# phone-finder.net
KiCad netlist of a schematic drawn in EAGLE
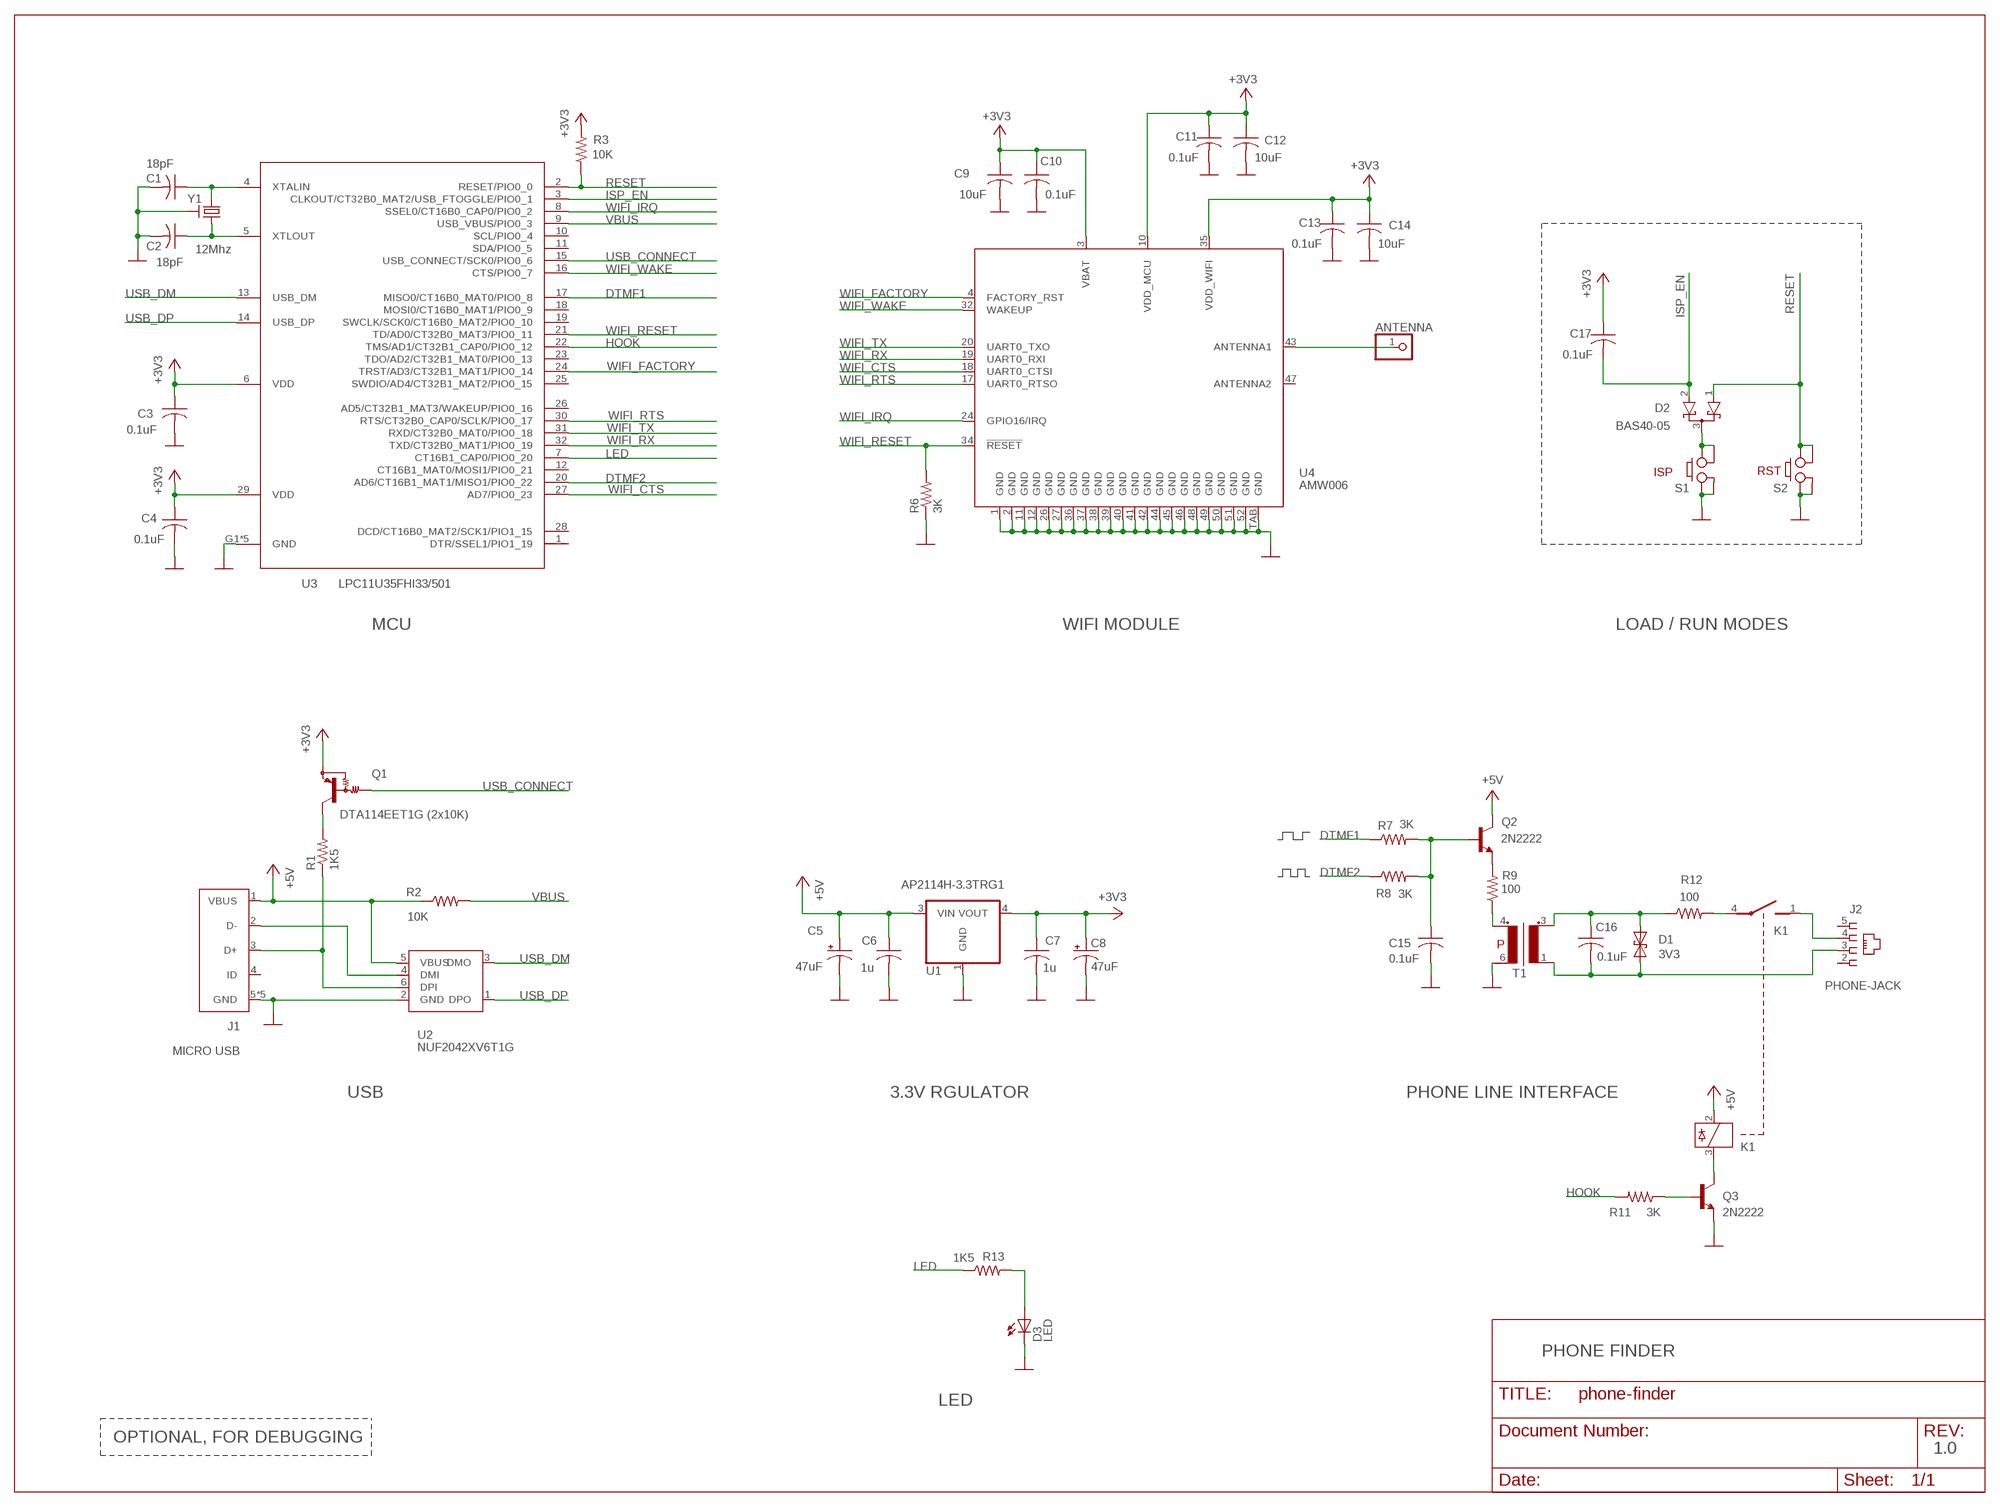
[diagram p0: schematic, sheet 1]

(export (version "E")
  (design (tool "Eeschema 10.0.6"))
  (components
    (comp (ref "ANTENNA")
      (value "PINHD-1X1")
      (footprint "eagle-import:PINHD-1X1")
      (libsource (lib "eagle-import") (part "PINHD-1X1"))
    )
    (comp (ref "C1")
      (value "18pF")
      (footprint "eagle-import:C0402K")
      (libsource (lib "eagle-import") (part "CC0402K"))
    )
    (comp (ref "C2")
      (value "18pF")
      (footprint "eagle-import:C0402K")
      (libsource (lib "eagle-import") (part "CC0402K"))
    )
    (comp (ref "C3")
      (value "0.1uF")
      (footprint "eagle-import:C0402K")
      (libsource (lib "eagle-import") (part "CC0402K"))
    )
    (comp (ref "C4")
      (value "0.1uF")
      (footprint "eagle-import:C0402K")
      (libsource (lib "eagle-import") (part "CC0402K"))
    )
    (comp (ref "C5")
      (value "47uF")
      (footprint "eagle-import:UD-6,3X5,8_NICHICON")
      (libsource (lib "eagle-import") (part "C-POLUD-6,3X5,8"))
    )
    (comp (ref "C6")
      (value "1u")
      (footprint "eagle-import:C0603K")
      (libsource (lib "eagle-import") (part "CC0603K"))
    )
    (comp (ref "C7")
      (value "1u")
      (footprint "eagle-import:C0603K")
      (libsource (lib "eagle-import") (part "CC0603K"))
    )
    (comp (ref "C8")
      (value "47uF")
      (footprint "eagle-import:UD-6,3X5,8_NICHICON")
      (libsource (lib "eagle-import") (part "C-POLUD-6,3X5,8"))
    )
    (comp (ref "C9")
      (value "10uF")
      (footprint "eagle-import:C0805K")
      (libsource (lib "eagle-import") (part "CC0805K"))
    )
    (comp (ref "C10")
      (value "0.1uF")
      (footprint "eagle-import:C0402K")
      (libsource (lib "eagle-import") (part "CC0402K"))
    )
    (comp (ref "C11")
      (value "0.1uF")
      (footprint "eagle-import:C0402K")
      (libsource (lib "eagle-import") (part "CC0402K"))
    )
    (comp (ref "C12")
      (value "10uF")
      (footprint "eagle-import:C0805K")
      (libsource (lib "eagle-import") (part "CC0805K"))
    )
    (comp (ref "C13")
      (value "0.1uF")
      (footprint "eagle-import:C0402K")
      (libsource (lib "eagle-import") (part "CC0402K"))
    )
    (comp (ref "C14")
      (value "10uF")
      (footprint "eagle-import:C0805K")
      (libsource (lib "eagle-import") (part "CC0805K"))
    )
    (comp (ref "C15")
      (value "0.1uF")
      (footprint "eagle-import:C0402K")
      (libsource (lib "eagle-import") (part "CC0402K"))
    )
    (comp (ref "C16")
      (value "0.1uF")
      (footprint "eagle-import:C0402K")
      (libsource (lib "eagle-import") (part "CC0402K"))
    )
    (comp (ref "C17")
      (value "0.1uF")
      (footprint "eagle-import:C0402K")
      (libsource (lib "eagle-import") (part "CC0402K"))
    )
    (comp (ref "D1")
      (value "3V3")
      (footprint "eagle-import:DZ-0402")
      (libsource (lib "eagle-import") (part "DUAL-ZENER"))
    )
    (comp (ref "D2")
      (value "BAS40-05")
      (footprint "eagle-import:SOT23")
      (libsource (lib "eagle-import") (part "BAS40-05"))
    )
    (comp (ref "D3")
      (value "LED")
      (footprint "eagle-import:LED")
      (libsource (lib "eagle-import") (part "LED"))
    )
    (comp (ref "J1")
      (value "MICRO USB")
      (footprint "eagle-import:USB-MICRO")
      (libsource (lib "eagle-import") (part "USB-CONN"))
    )
    (comp (ref "J2")
      (value "PHONE-JACK")
      (footprint "eagle-import:PHONE-JACK")
      (libsource (lib "eagle-import") (part "PHONE-JACK"))
    )
    (comp (ref "K1")
      (value "RELAY")
      (footprint "eagle-import:RELAY")
      (libsource (lib "eagle-import") (part "RELAY"))
    )
    (comp (ref "Q1")
      (value "DTA114EET1G (2x10K)")
      (footprint "eagle-import:SC75-BEC")
      (libsource (lib "eagle-import") (part "PNP-BIASED"))
    )
    (comp (ref "Q2")
      (value "2N2222")
      (footprint "eagle-import:SOT23")
      (libsource (lib "eagle-import") (part "NPN"))
    )
    (comp (ref "Q3")
      (value "2N2222")
      (footprint "eagle-import:SOT23")
      (libsource (lib "eagle-import") (part "NPN"))
    )
    (comp (ref "R1")
      (value "1K5")
      (footprint "eagle-import:R0402")
      (libsource (lib "eagle-import") (part "RR0402"))
    )
    (comp (ref "R2")
      (value "10K")
      (footprint "eagle-import:R0402")
      (libsource (lib "eagle-import") (part "RR0402"))
    )
    (comp (ref "R3")
      (value "10K")
      (footprint "eagle-import:R0402")
      (libsource (lib "eagle-import") (part "RR0402"))
    )
    (comp (ref "R6")
      (value "3K")
      (footprint "eagle-import:R0402")
      (libsource (lib "eagle-import") (part "RR0402"))
    )
    (comp (ref "R7")
      (value "3K")
      (footprint "eagle-import:R0402")
      (libsource (lib "eagle-import") (part "RR0402"))
    )
    (comp (ref "R8")
      (value "3K")
      (footprint "eagle-import:R0402")
      (libsource (lib "eagle-import") (part "RR0402"))
    )
    (comp (ref "R9")
      (value "100")
      (footprint "eagle-import:R0805")
      (libsource (lib "eagle-import") (part "RR0805"))
    )
    (comp (ref "R11")
      (value "3K")
      (footprint "eagle-import:R0402")
      (libsource (lib "eagle-import") (part "RR0402"))
    )
    (comp (ref "R12")
      (value "100")
      (footprint "eagle-import:R0805")
      (libsource (lib "eagle-import") (part "RR0805"))
    )
    (comp (ref "R13")
      (value "1K5")
      (footprint "eagle-import:R0402")
      (libsource (lib "eagle-import") (part "RR0402"))
    )
    (comp (ref "S1")
      (value "PUSH-BUTTON")
      (footprint "eagle-import:PUSH_BUTTON")
      (libsource (lib "eagle-import") (part "PUSH-BUTTON"))
    )
    (comp (ref "S2")
      (value "PUSH-BUTTON")
      (footprint "eagle-import:PUSH_BUTTON")
      (libsource (lib "eagle-import") (part "PUSH-BUTTON"))
    )
    (comp (ref "T1")
      (value "TRANSFORMER")
      (footprint "eagle-import:TRANSFORMER")
      (libsource (lib "eagle-import") (part "TRANSFORMER"))
    )
    (comp (ref "U1")
      (value "AP2114H-3.3TRG1")
      (footprint "eagle-import:SOT223")
      (libsource (lib "eagle-import") (part "LDOSOT223"))
    )
    (comp (ref "U2")
      (value "NUF2042XV6T1G")
      (footprint "eagle-import:SOT-563")
      (libsource (lib "eagle-import") (part "USB-ESD"))
    )
    (comp (ref "U3")
      (value "LPC11U35FHI33/501")
      (footprint "eagle-import:HVQFN33-5MM")
      (libsource (lib "eagle-import") (part "LPC11U35FHN33/501"))
    )
    (comp (ref "U4")
      (value "AMW006")
      (footprint "eagle-import:WIFI_MODULE")
      (libsource (lib "eagle-import") (part "WIFI-MODULESMT"))
    )
    (comp (ref "Y1")
      (value "12Mhz")
      (footprint "eagle-import:CRYSTAL")
      (libsource (lib "eagle-import") (part "CRYSTALCTS406"))
    )
  )
  (nets
    (net (code "1") (name "+3V3") (class "Default")
      (node (ref "C10") (pin "1") (pinfunction "1_1") (pintype "passive"))
      (node (ref "C11") (pin "1") (pinfunction "1_1") (pintype "passive"))
      (node (ref "C12") (pin "1") (pinfunction "1_1") (pintype "passive"))
      (node (ref "C13") (pin "1") (pinfunction "1_1") (pintype "passive"))
      (node (ref "C14") (pin "1") (pinfunction "1_1") (pintype "passive"))
      (node (ref "C17") (pin "1") (pinfunction "1_1") (pintype "passive"))
      (node (ref "C3") (pin "1") (pinfunction "1_1") (pintype "passive"))
      (node (ref "C4") (pin "1") (pinfunction "1_1") (pintype "passive"))
      (node (ref "C7") (pin "1") (pinfunction "1_1") (pintype "passive"))
      (node (ref "C8") (pin "+") (pinfunction "+_+") (pintype "passive"))
      (node (ref "C9") (pin "1") (pinfunction "1_1") (pintype "passive"))
      (node (ref "Q1") (pin "E") (pinfunction "E_E") (pintype "passive"))
      (node (ref "R3") (pin "2") (pinfunction "2_2") (pintype "passive"))
      (node (ref "U1") (pin "4") (pinfunction "VOUT_4") (pintype "power_in"))
      (node (ref "U3") (pin "29") (pinfunction "VDD_29") (pintype "bidirectional"))
      (node (ref "U3") (pin "6") (pinfunction "VDD_6") (pintype "bidirectional"))
      (node (ref "U4") (pin "10") (pinfunction "VDD_MCU_10") (pintype "power_in"))
      (node (ref "U4") (pin "3") (pinfunction "VBAT_3") (pintype "power_in"))
      (node (ref "U4") (pin "35") (pinfunction "VDD_WIFI_35") (pintype "power_in"))
    )
    (net (code "2") (name "+5V") (class "Default")
      (node (ref "C5") (pin "+") (pinfunction "+_+") (pintype "passive"))
      (node (ref "C6") (pin "1") (pinfunction "1_1") (pintype "passive"))
      (node (ref "J1") (pin "1") (pinfunction "VBUS_1") (pintype "bidirectional"))
      (node (ref "K1") (pin "2") (pinfunction "COIL-POS_2") (pintype "passive"))
      (node (ref "Q2") (pin "3") (pinfunction "C_3") (pintype "passive"))
      (node (ref "R2") (pin "1") (pinfunction "1_1") (pintype "passive"))
      (node (ref "U1") (pin "3") (pinfunction "VIN_3") (pintype "power_in"))
      (node (ref "U2") (pin "5") (pinfunction "VBUS_5") (pintype "power_in"))
    )
    (net (code "3") (name "/DTMF1") (class "Default")
      (node (ref "R7") (pin "1") (pinfunction "1_1") (pintype "passive"))
      (node (ref "U3") (pin "17") (pinfunction "MISO0/CT16B0_MAT0/PIO0_8_17") (pintype "bidirectional"))
    )
    (net (code "4") (name "/DTMF2") (class "Default")
      (node (ref "R8") (pin "1") (pinfunction "1_1") (pintype "passive"))
      (node (ref "U3") (pin "20") (pinfunction "AD6/CT16B1_MAT1/MISO1/PIO0_22_20") (pintype "bidirectional"))
    )
    (net (code "5") (name "/HOOK") (class "Default")
      (node (ref "R11") (pin "2") (pinfunction "2_2") (pintype "passive"))
      (node (ref "U3") (pin "22") (pinfunction "TMS/AD1/CT32B1_CAP0/PIO0_12_22") (pintype "bidirectional"))
    )
    (net (code "6") (name "/ISP_EN") (class "Default")
      (node (ref "C17") (pin "2") (pinfunction "2_2") (pintype "passive"))
      (node (ref "D2") (pin "2") (pinfunction "A2_2") (pintype "passive"))
      (node (ref "U3") (pin "3") (pinfunction "CLKOUT/CT32B0_MAT2/USB_FTOGGLE/PIO0_1_3") (pintype "bidirectional"))
    )
    (net (code "7") (name "/LED") (class "Default")
      (node (ref "R13") (pin "1") (pinfunction "1_1") (pintype "passive"))
      (node (ref "U3") (pin "7") (pinfunction "CT16B1_CAP0/PIO0_20_7") (pintype "bidirectional"))
    )
    (net (code "8") (name "/RESET") (class "Default")
      (node (ref "D2") (pin "1") (pinfunction "A1_1") (pintype "passive"))
      (node (ref "R3") (pin "1") (pinfunction "1_1") (pintype "passive"))
      (node (ref "S2") (pin "B1") (pinfunction "B1_B1") (pintype "passive"))
      (node (ref "S2") (pin "B1P") (pinfunction "B1_B1P") (pintype "passive"))
      (node (ref "S2") (pin "B2") (pinfunction "B2_B2") (pintype "passive"))
      (node (ref "S2") (pin "B2P") (pinfunction "B2_B2P") (pintype "passive"))
      (node (ref "U3") (pin "2") (pinfunction "RESET/PIO0_0_2") (pintype "bidirectional"))
    )
    (net (code "9") (name "/USB_CONNECT") (class "Default")
      (node (ref "Q1") (pin "B") (pinfunction "B_B") (pintype "passive"))
      (node (ref "U3") (pin "15") (pinfunction "USB_CONNECT/SCK0/PIO0_6_15") (pintype "bidirectional"))
    )
    (net (code "10") (name "/USB_DM") (class "Default")
      (node (ref "U2") (pin "3") (pinfunction "DMO_3") (pintype "passive"))
      (node (ref "U3") (pin "13") (pinfunction "USB_DM_13") (pintype "bidirectional"))
    )
    (net (code "11") (name "/USB_DP") (class "Default")
      (node (ref "U2") (pin "1") (pinfunction "DPO_1") (pintype "passive"))
      (node (ref "U3") (pin "14") (pinfunction "USB_DP_14") (pintype "bidirectional"))
    )
    (net (code "12") (name "/VBUS") (class "Default")
      (node (ref "R2") (pin "2") (pinfunction "2_2") (pintype "passive"))
      (node (ref "U3") (pin "9") (pinfunction "USB_VBUS/PIO0_3_9") (pintype "bidirectional"))
    )
    (net (code "13") (name "/WIFI_CTS") (class "Default")
      (node (ref "U3") (pin "27") (pinfunction "AD7/PIO0_23_27") (pintype "bidirectional"))
      (node (ref "U4") (pin "18") (pinfunction "UART0_CTSI_18") (pintype "input"))
    )
    (net (code "14") (name "/WIFI_FACTORY") (class "Default")
      (node (ref "U3") (pin "24") (pinfunction "TRST/AD3/CT32B1_MAT1/PIO0_14_24") (pintype "bidirectional"))
      (node (ref "U4") (pin "4") (pinfunction "FACTORY_RST_4") (pintype "input"))
    )
    (net (code "15") (name "/WIFI_IRQ") (class "Default")
      (node (ref "U3") (pin "8") (pinfunction "SSEL0/CT16B0_CAP0/PIO0_2_8") (pintype "bidirectional"))
      (node (ref "U4") (pin "24") (pinfunction "GPIO16/IRQ_24") (pintype "output"))
    )
    (net (code "16") (name "/WIFI_RESET") (class "Default")
      (node (ref "R6") (pin "2") (pinfunction "2_2") (pintype "passive"))
      (node (ref "U3") (pin "21") (pinfunction "TD/AD0/CT32B0_MAT3/PIO0_11_21") (pintype "bidirectional"))
      (node (ref "U4") (pin "34") (pinfunction "~{RESET}_34") (pintype "input"))
    )
    (net (code "17") (name "/WIFI_RTS") (class "Default")
      (node (ref "U3") (pin "30") (pinfunction "RTS/CT32B0_CAP0/SCLK/PIO0_17_30") (pintype "bidirectional"))
      (node (ref "U4") (pin "17") (pinfunction "UART0_RTSO_17") (pintype "output"))
    )
    (net (code "18") (name "/WIFI_RX") (class "Default")
      (node (ref "U3") (pin "32") (pinfunction "TXD/CT32B0_MAT1/PIO0_19_32") (pintype "bidirectional"))
      (node (ref "U4") (pin "19") (pinfunction "UART0_RXI_19") (pintype "input"))
    )
    (net (code "19") (name "/WIFI_TX") (class "Default")
      (node (ref "U3") (pin "31") (pinfunction "RXD/CT32B0_MAT0/PIO0_18_31") (pintype "bidirectional"))
      (node (ref "U4") (pin "20") (pinfunction "UART0_TXO_20") (pintype "output"))
    )
    (net (code "20") (name "/WIFI_WAKE") (class "Default")
      (node (ref "U3") (pin "16") (pinfunction "CTS/PIO0_7_16") (pintype "bidirectional"))
      (node (ref "U4") (pin "32") (pinfunction "WAKEUP_32") (pintype "input"))
    )
    (net (code "21") (name "GND") (class "Default")
      (node (ref "C1") (pin "2") (pinfunction "2_2") (pintype "passive"))
      (node (ref "C10") (pin "2") (pinfunction "2_2") (pintype "passive"))
      (node (ref "C11") (pin "2") (pinfunction "2_2") (pintype "passive"))
      (node (ref "C12") (pin "2") (pinfunction "2_2") (pintype "passive"))
      (node (ref "C13") (pin "2") (pinfunction "2_2") (pintype "passive"))
      (node (ref "C14") (pin "2") (pinfunction "2_2") (pintype "passive"))
      (node (ref "C15") (pin "2") (pinfunction "2_2") (pintype "passive"))
      (node (ref "C2") (pin "2") (pinfunction "2_2") (pintype "passive"))
      (node (ref "C3") (pin "2") (pinfunction "2_2") (pintype "passive"))
      (node (ref "C4") (pin "2") (pinfunction "2_2") (pintype "passive"))
      (node (ref "C5") (pin "-") (pinfunction "-_-") (pintype "passive"))
      (node (ref "C6") (pin "2") (pinfunction "2_2") (pintype "passive"))
      (node (ref "C7") (pin "2") (pinfunction "2_2") (pintype "passive"))
      (node (ref "C8") (pin "-") (pinfunction "-_-") (pintype "passive"))
      (node (ref "C9") (pin "2") (pinfunction "2_2") (pintype "passive"))
      (node (ref "D3") (pin "K") (pinfunction "C_K") (pintype "passive"))
      (node (ref "J1") (pin "5") (pinfunction "GND_5") (pintype "bidirectional"))
      (node (ref "J1") (pin "G1") (pinfunction "GND_G1") (pintype "bidirectional"))
      (node (ref "J1") (pin "G2") (pinfunction "GND_G2") (pintype "bidirectional"))
      (node (ref "J1") (pin "G3") (pinfunction "GND_G3") (pintype "bidirectional"))
      (node (ref "J1") (pin "G4") (pinfunction "GND_G4") (pintype "bidirectional"))
      (node (ref "Q3") (pin "2") (pinfunction "E_2") (pintype "passive"))
      (node (ref "R6") (pin "1") (pinfunction "1_1") (pintype "passive"))
      (node (ref "S1") (pin "A1") (pinfunction "A1_A1") (pintype "passive"))
      (node (ref "S1") (pin "A1P") (pinfunction "A1_A1P") (pintype "passive"))
      (node (ref "S1") (pin "A2") (pinfunction "A2_A2") (pintype "passive"))
      (node (ref "S1") (pin "A2P") (pinfunction "A2_A2P") (pintype "passive"))
      (node (ref "S2") (pin "A1") (pinfunction "A1_A1") (pintype "passive"))
      (node (ref "S2") (pin "A1P") (pinfunction "A1_A1P") (pintype "passive"))
      (node (ref "S2") (pin "A2") (pinfunction "A2_A2") (pintype "passive"))
      (node (ref "S2") (pin "A2P") (pinfunction "A2_A2P") (pintype "passive"))
      (node (ref "T1") (pin "6") (pinfunction "P2_6") (pintype "passive"))
      (node (ref "U1") (pin "1") (pinfunction "GND_1") (pintype "power_in"))
      (node (ref "U2") (pin "2") (pinfunction "GND_2") (pintype "power_in"))
      (node (ref "U3") (pin "G1") (pinfunction "GND_G1") (pintype "bidirectional"))
      (node (ref "U3") (pin "G2") (pinfunction "GND_G2") (pintype "bidirectional"))
      (node (ref "U3") (pin "G3") (pinfunction "GND_G3") (pintype "bidirectional"))
      (node (ref "U3") (pin "G4") (pinfunction "GND_G4") (pintype "bidirectional"))
      (node (ref "U3") (pin "TAB") (pinfunction "GND_TAB") (pintype "bidirectional"))
      (node (ref "U4") (pin "1") (pinfunction "GND_1") (pintype "power_in"))
      (node (ref "U4") (pin "11") (pinfunction "GND_11") (pintype "power_in"))
      (node (ref "U4") (pin "12") (pinfunction "GND_12") (pintype "power_in"))
      (node (ref "U4") (pin "2") (pinfunction "GND_2") (pintype "power_in"))
      (node (ref "U4") (pin "26") (pinfunction "GND_26") (pintype "power_in"))
      (node (ref "U4") (pin "27") (pinfunction "GND_27") (pintype "power_in"))
      (node (ref "U4") (pin "36") (pinfunction "GND_36") (pintype "power_in"))
      (node (ref "U4") (pin "37") (pinfunction "GND_37") (pintype "power_in"))
      (node (ref "U4") (pin "38") (pinfunction "GND_38") (pintype "power_in"))
      (node (ref "U4") (pin "39") (pinfunction "GND_39") (pintype "power_in"))
      (node (ref "U4") (pin "40") (pinfunction "GND_40") (pintype "power_in"))
      (node (ref "U4") (pin "41") (pinfunction "GND_41") (pintype "power_in"))
      (node (ref "U4") (pin "42") (pinfunction "GND_42") (pintype "power_in"))
      (node (ref "U4") (pin "44") (pinfunction "GND_44") (pintype "power_in"))
      (node (ref "U4") (pin "45") (pinfunction "GND_45") (pintype "power_in"))
      (node (ref "U4") (pin "46") (pinfunction "GND_46") (pintype "power_in"))
      (node (ref "U4") (pin "48") (pinfunction "GND_48") (pintype "power_in"))
      (node (ref "U4") (pin "49") (pinfunction "GND_49") (pintype "power_in"))
      (node (ref "U4") (pin "50") (pinfunction "GND_50") (pintype "power_in"))
      (node (ref "U4") (pin "51") (pinfunction "GND_51") (pintype "power_in"))
      (node (ref "U4") (pin "52") (pinfunction "GND_52") (pintype "power_in"))
      (node (ref "U4") (pin "TAB") (pinfunction "GND_TAB") (pintype "power_in"))
      (node (ref "Y1") (pin "2") (pinfunction "GND_2") (pintype "power_in"))
      (node (ref "Y1") (pin "4") (pinfunction "GND_4") (pintype "power_in"))
    )
    (net (code "22") (name "Net-(D2-C)") (class "Default")
      (node (ref "D2") (pin "3") (pinfunction "C_3") (pintype "passive"))
      (node (ref "S1") (pin "B1") (pinfunction "B1_B1") (pintype "passive"))
      (node (ref "S1") (pin "B1P") (pinfunction "B1_B1P") (pintype "passive"))
      (node (ref "S1") (pin "B2") (pinfunction "B2_B2") (pintype "passive"))
      (node (ref "S1") (pin "B2P") (pinfunction "B2_B2P") (pintype "passive"))
    )
    (net (code "23") (name "Net-(D3-PadA)") (class "Default")
      (node (ref "D3") (pin "A") (pinfunction "A_A") (pintype "passive"))
      (node (ref "R13") (pin "2") (pinfunction "2_2") (pintype "passive"))
    )
    (net (code "24") (name "Net-(J1-D+)") (class "Default")
      (node (ref "J1") (pin "3") (pinfunction "D+_3") (pintype "bidirectional"))
      (node (ref "R1") (pin "1") (pinfunction "1_1") (pintype "passive"))
      (node (ref "U2") (pin "6") (pinfunction "DPI_6") (pintype "passive"))
    )
    (net (code "25") (name "Net-(J1-D-)") (class "Default")
      (node (ref "J1") (pin "2") (pinfunction "D-_2") (pintype "bidirectional"))
      (node (ref "U2") (pin "4") (pinfunction "DMI_4") (pintype "passive"))
    )
    (net (code "26") (name "Net-(K1A-COIL-NEG)") (class "Default")
      (node (ref "K1") (pin "3") (pinfunction "COIL-NEG_3") (pintype "passive"))
      (node (ref "Q3") (pin "3") (pinfunction "C_3") (pintype "passive"))
    )
    (net (code "27") (name "Net-(K1B-S1)") (class "Default")
      (node (ref "J2") (pin "4") (pinfunction "4_4") (pintype "passive"))
      (node (ref "K1") (pin "1") (pinfunction "S1_1") (pintype "passive"))
    )
    (net (code "28") (name "Net-(K1B-S2)") (class "Default")
      (node (ref "K1") (pin "4") (pinfunction "S2_4") (pintype "passive"))
      (node (ref "R12") (pin "2") (pinfunction "2_2") (pintype "passive"))
    )
    (net (code "29") (name "Net-(Q1-PadC)") (class "Default")
      (node (ref "Q1") (pin "C") (pinfunction "C_C") (pintype "passive"))
      (node (ref "R1") (pin "2") (pinfunction "2_2") (pintype "passive"))
    )
    (net (code "30") (name "Net-(Q2-B)") (class "Default")
      (node (ref "C15") (pin "1") (pinfunction "1_1") (pintype "passive"))
      (node (ref "Q2") (pin "1") (pinfunction "B_1") (pintype "passive"))
      (node (ref "R7") (pin "2") (pinfunction "2_2") (pintype "passive"))
      (node (ref "R8") (pin "2") (pinfunction "2_2") (pintype "passive"))
    )
    (net (code "31") (name "Net-(Q2-E)") (class "Default")
      (node (ref "Q2") (pin "2") (pinfunction "E_2") (pintype "passive"))
      (node (ref "R9") (pin "2") (pinfunction "2_2") (pintype "passive"))
    )
    (net (code "32") (name "Net-(Q3-B)") (class "Default")
      (node (ref "Q3") (pin "1") (pinfunction "B_1") (pintype "passive"))
      (node (ref "R11") (pin "1") (pinfunction "1_1") (pintype "passive"))
    )
    (net (code "33") (name "Net-(T1-P1)") (class "Default")
      (node (ref "R9") (pin "1") (pinfunction "1_1") (pintype "passive"))
      (node (ref "T1") (pin "4") (pinfunction "P1_4") (pintype "passive"))
    )
    (net (code "34") (name "Net-(T1-S1)") (class "Default")
      (node (ref "C16") (pin "1") (pinfunction "1_1") (pintype "passive"))
      (node (ref "D1") (pin "2") (pinfunction "2_2") (pintype "passive"))
      (node (ref "R12") (pin "1") (pinfunction "1_1") (pintype "passive"))
      (node (ref "T1") (pin "3") (pinfunction "S1_3") (pintype "passive"))
    )
    (net (code "35") (name "Net-(T1-S2)") (class "Default")
      (node (ref "C16") (pin "2") (pinfunction "2_2") (pintype "passive"))
      (node (ref "D1") (pin "1") (pinfunction "1_1") (pintype "passive"))
      (node (ref "J2") (pin "3") (pinfunction "3_3") (pintype "passive"))
      (node (ref "T1") (pin "1") (pinfunction "S2_1") (pintype "passive"))
    )
    (net (code "36") (name "Net-(U3-XTALIN)") (class "Default")
      (node (ref "C1") (pin "1") (pinfunction "1_1") (pintype "passive"))
      (node (ref "U3") (pin "4") (pinfunction "XTALIN_4") (pintype "bidirectional"))
      (node (ref "Y1") (pin "3") (pinfunction "2_3") (pintype "passive"))
    )
    (net (code "37") (name "Net-(U3-XTLOUT)") (class "Default")
      (node (ref "C2") (pin "1") (pinfunction "1_1") (pintype "passive"))
      (node (ref "U3") (pin "5") (pinfunction "XTLOUT_5") (pintype "bidirectional"))
      (node (ref "Y1") (pin "1") (pinfunction "1_1") (pintype "passive"))
    )
    (net (code "38") (name "Net-(U4-ANTENNA1)") (class "Default")
      (node (ref "ANTENNA") (pin "1") (pinfunction "1_1") (pintype "passive"))
      (node (ref "U4") (pin "43") (pinfunction "ANTENNA1_43") (pintype "passive"))
    )
    (net (code "39") (name "unconnected-(J1-ID-Pad4)") (class "Default")
      (node (ref "J1") (pin "4") (pinfunction "ID_4") (pintype "bidirectional"))
    )
    (net (code "40") (name "unconnected-(J2-Pad2)") (class "Default")
      (node (ref "J2") (pin "2") (pinfunction "2_2") (pintype "passive"))
    )
    (net (code "41") (name "unconnected-(J2-Pad5)") (class "Default")
      (node (ref "J2") (pin "5") (pinfunction "5_5") (pintype "passive"))
    )
    (net (code "42") (name "unconnected-(U3-AD5{slash}CT32B1_MAT3{slash}WAKEUP{slash}PIO0_16-Pad26)") (class "Default")
      (node (ref "U3") (pin "26") (pinfunction "AD5/CT32B1_MAT3/WAKEUP/PIO0_16_26") (pintype "bidirectional"))
    )
    (net (code "43") (name "unconnected-(U3-CT16B1_MAT0{slash}MOSI1{slash}PIO0_21-Pad12)") (class "Default")
      (node (ref "U3") (pin "12") (pinfunction "CT16B1_MAT0/MOSI1/PIO0_21_12") (pintype "bidirectional"))
    )
    (net (code "44") (name "unconnected-(U3-DCD{slash}CT16B0_MAT2{slash}SCK1{slash}PIO1_15-Pad28)") (class "Default")
      (node (ref "U3") (pin "28") (pinfunction "DCD/CT16B0_MAT2/SCK1/PIO1_15_28") (pintype "bidirectional"))
    )
    (net (code "45") (name "unconnected-(U3-DTR{slash}SSEL1{slash}PIO1_19-Pad1)") (class "Default")
      (node (ref "U3") (pin "1") (pinfunction "DTR/SSEL1/PIO1_19_1") (pintype "bidirectional"))
    )
    (net (code "46") (name "unconnected-(U3-MOSI0{slash}CT16B0_MAT1{slash}PIO0_9-Pad18)") (class "Default")
      (node (ref "U3") (pin "18") (pinfunction "MOSI0/CT16B0_MAT1/PIO0_9_18") (pintype "bidirectional"))
    )
    (net (code "47") (name "unconnected-(U3-SCL{slash}PIO0_4-Pad10)") (class "Default")
      (node (ref "U3") (pin "10") (pinfunction "SCL/PIO0_4_10") (pintype "bidirectional"))
    )
    (net (code "48") (name "unconnected-(U3-SDA{slash}PIO0_5-Pad11)") (class "Default")
      (node (ref "U3") (pin "11") (pinfunction "SDA/PIO0_5_11") (pintype "bidirectional"))
    )
    (net (code "49") (name "unconnected-(U3-SWCLK{slash}SCK0{slash}CT16B0_MAT2{slash}PIO0_10-Pad19)") (class "Default")
      (node (ref "U3") (pin "19") (pinfunction "SWCLK/SCK0/CT16B0_MAT2/PIO0_10_19") (pintype "bidirectional"))
    )
    (net (code "50") (name "unconnected-(U3-SWDIO{slash}AD4{slash}CT32B1_MAT2{slash}PIO0_15-Pad25)") (class "Default")
      (node (ref "U3") (pin "25") (pinfunction "SWDIO/AD4/CT32B1_MAT2/PIO0_15_25") (pintype "bidirectional"))
    )
    (net (code "51") (name "unconnected-(U3-TDO{slash}AD2{slash}CT32B1_MAT0{slash}PIO0_13-Pad23)") (class "Default")
      (node (ref "U3") (pin "23") (pinfunction "TDO/AD2/CT32B1_MAT0/PIO0_13_23") (pintype "bidirectional"))
    )
    (net (code "52") (name "unconnected-(U4-ANTENNA2-Pad47)") (class "Default")
      (node (ref "U4") (pin "47") (pinfunction "ANTENNA2_47") (pintype "passive"))
    )
  )
)
